# RLC.net
KiCad netlist of a schematic drawn in Altium Designer
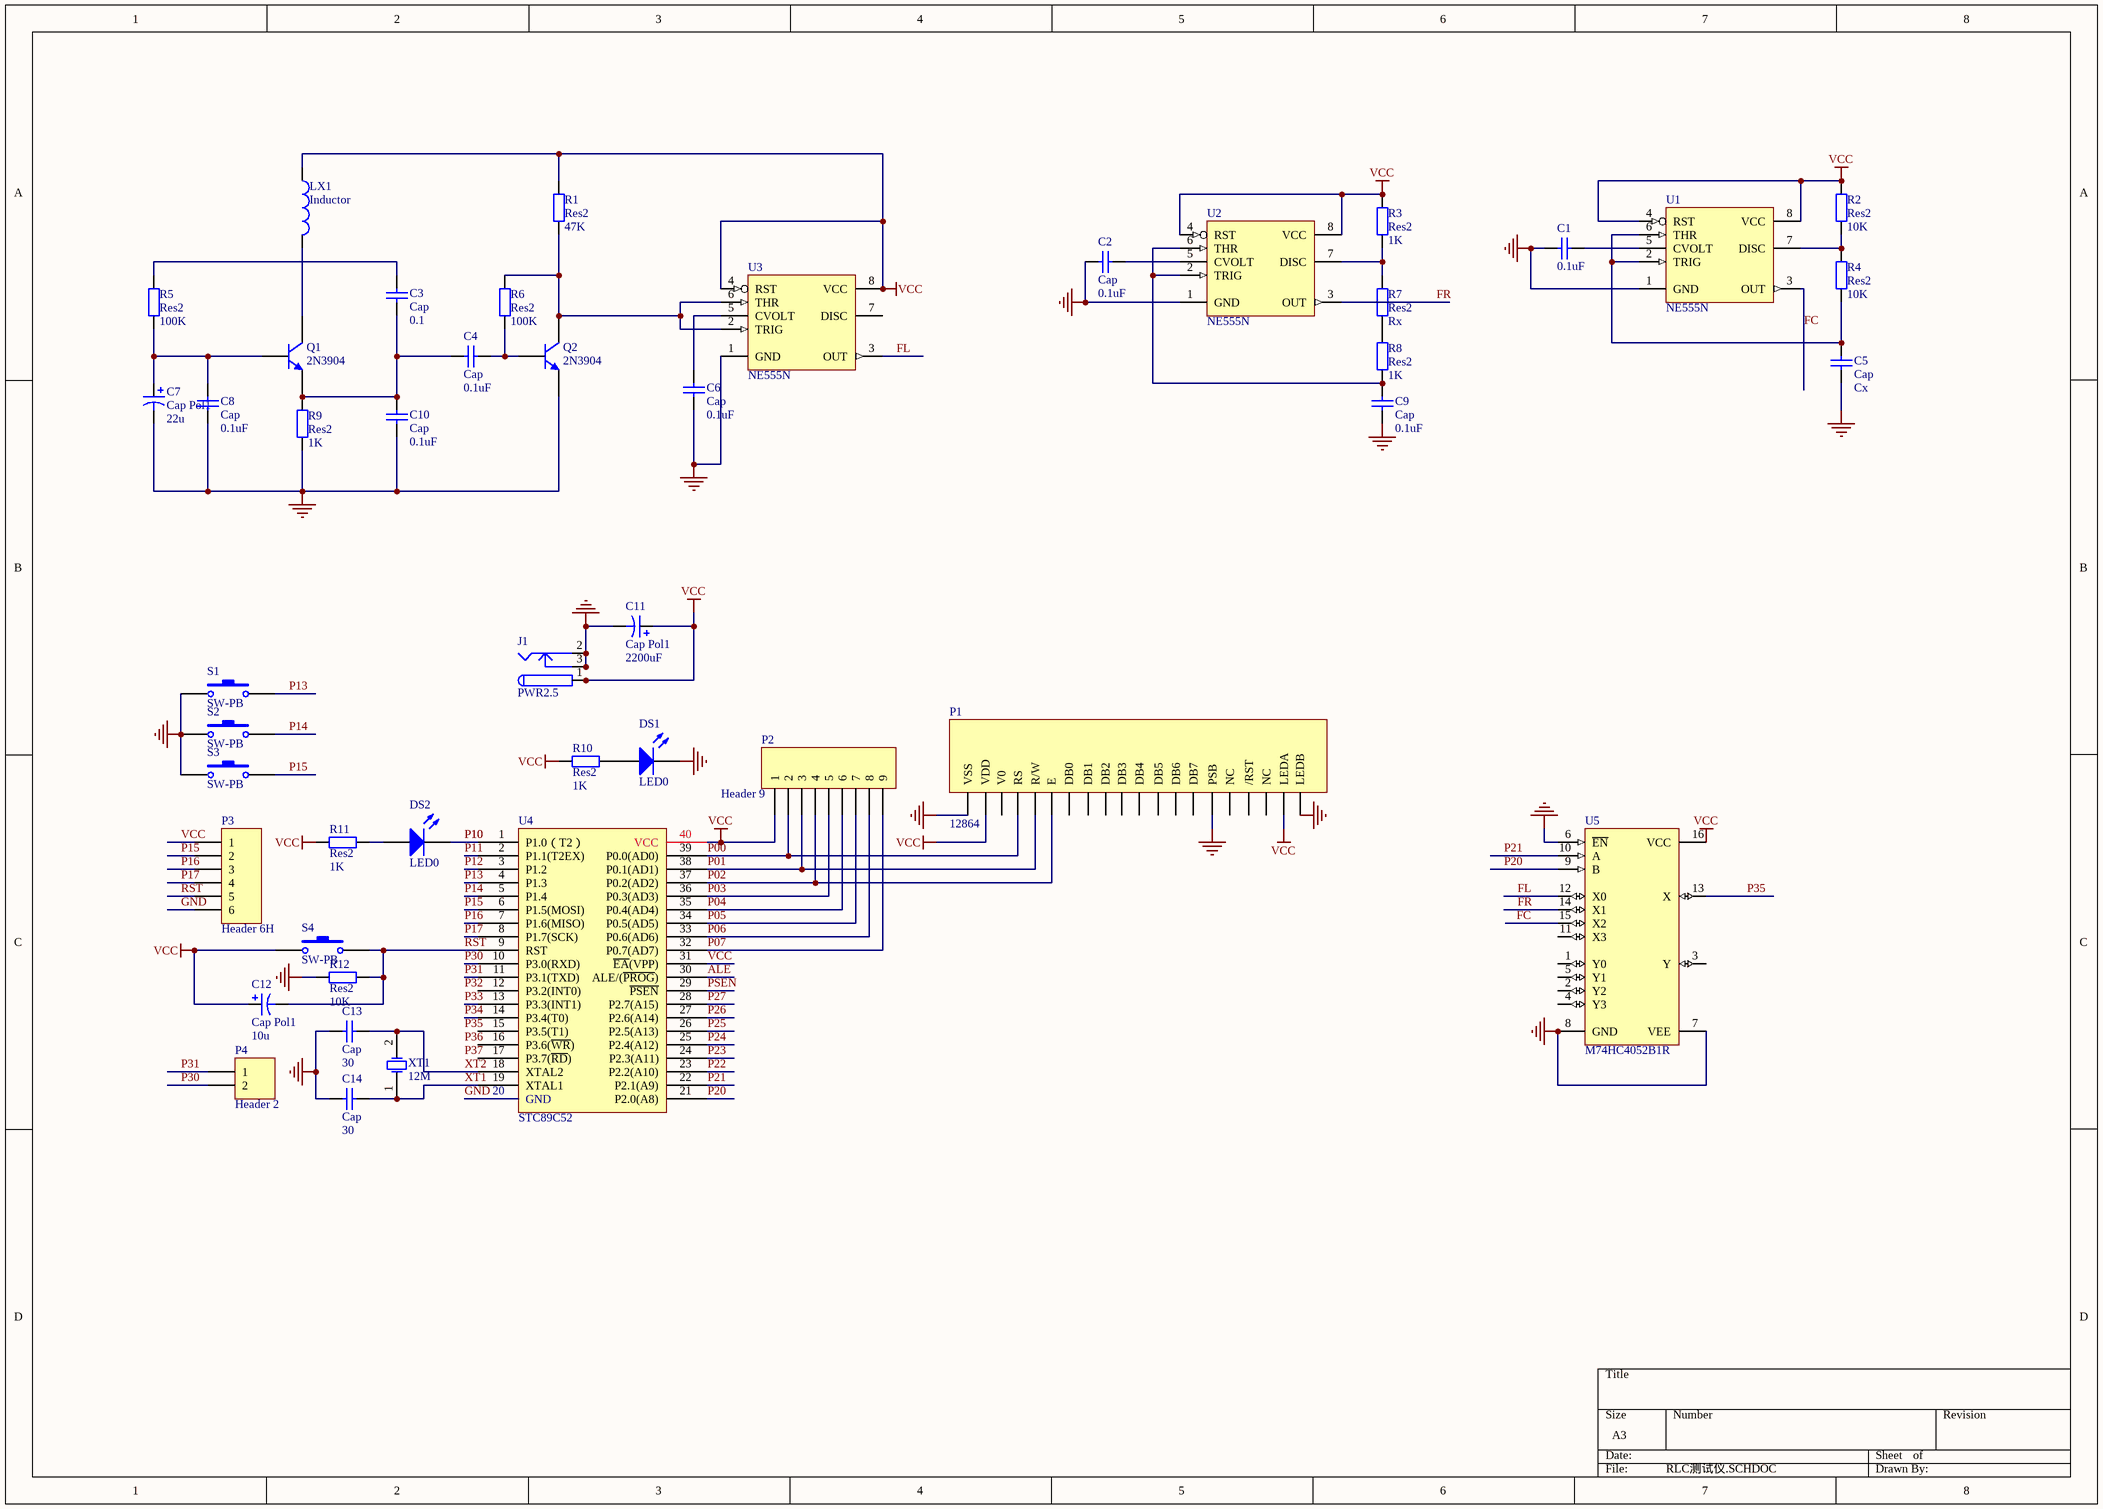
[diagram p0: RLC测试仪.SCHDOC]

(export (version "E")
  (design (tool "Eeschema 10.0.6"))
  (components
    (comp (ref "C1")
      (value "0.1uF")
      (footprint "RAD-0.2")
      (description "Capacitor")
      (fields (field (name "PUBLISHER") "Altium Limited"))
      (libsource (lib "Miscellaneous Devices") (part "Cap"))
    )
    (comp (ref "C2")
      (value "Cap")
      (footprint "RAD-0.2")
      (description "Capacitor")
      (fields (field (name "ALTIUM_VALUE") "0.1uF") (field (name "PUBLISHER") "Altium Limited"))
      (libsource (lib "Miscellaneous Devices") (part "Cap"))
    )
    (comp (ref "C3")
      (value "Cap")
      (footprint "RAD-0.2")
      (description "Capacitor")
      (fields (field (name "ALTIUM_VALUE") "0.1") (field (name "PUBLISHER") "Altium Limited"))
      (libsource (lib "Miscellaneous Devices") (part "Cap"))
    )
    (comp (ref "C4")
      (value "Cap")
      (footprint "RAD-0.2")
      (description "Capacitor")
      (fields (field (name "ALTIUM_VALUE") "0.1uF") (field (name "PUBLISHER") "Altium Limited"))
      (libsource (lib "Miscellaneous Devices") (part "Cap"))
    )
    (comp (ref "C5")
      (value "Cap")
      (footprint "RAD-0.2")
      (description "Capacitor")
      (fields (field (name "ALTIUM_VALUE") "Cx") (field (name "PUBLISHER") "Altium Limited"))
      (libsource (lib "Miscellaneous Devices") (part "Cap"))
    )
    (comp (ref "C6")
      (value "Cap")
      (footprint "RAD-0.2")
      (description "Capacitor")
      (fields (field (name "ALTIUM_VALUE") "0.1uF") (field (name "PUBLISHER") "Altium Limited"))
      (libsource (lib "Miscellaneous Devices") (part "Cap"))
    )
    (comp (ref "C7")
      (value "Cap Pol1")
      (footprint "电容")
      (description "Polarized Capacitor (Radial)")
      (fields (field (name "ALTIUM_VALUE") "22u") (field (name "PUBLISHER") "Altium Limited"))
      (libsource (lib "Miscellaneous Devices") (part "Cap Pol1"))
    )
    (comp (ref "C8")
      (value "Cap")
      (footprint "RAD-0.2")
      (description "Capacitor")
      (fields (field (name "ALTIUM_VALUE") "0.1uF") (field (name "PUBLISHER") "Altium Limited"))
      (libsource (lib "Miscellaneous Devices") (part "Cap"))
    )
    (comp (ref "C9")
      (value "Cap")
      (footprint "RAD-0.2")
      (description "Capacitor")
      (fields (field (name "ALTIUM_VALUE") "0.1uF") (field (name "PUBLISHER") "Altium Limited"))
      (libsource (lib "Miscellaneous Devices") (part "Cap"))
    )
    (comp (ref "C10")
      (value "Cap")
      (footprint "RAD-0.2")
      (description "Capacitor")
      (fields (field (name "ALTIUM_VALUE") "0.1uF") (field (name "PUBLISHER") "Altium Limited"))
      (libsource (lib "Miscellaneous Devices") (part "Cap"))
    )
    (comp (ref "C11")
      (value "Cap Pol1")
      (footprint "电容")
      (description "Polarized Capacitor (Radial)")
      (fields (field (name "ALTIUM_VALUE") "2200uF") (field (name "PUBLISHER") "Altium Limited"))
      (libsource (lib "Miscellaneous Devices") (part "Cap Pol1"))
    )
    (comp (ref "C12")
      (value "Cap Pol1")
      (footprint "电容")
      (description "Polarized Capacitor (Radial)")
      (fields (field (name "ALTIUM_VALUE") "10u") (field (name "PUBLISHER") "Altium Limited"))
      (libsource (lib "Miscellaneous Devices") (part "Cap Pol1"))
    )
    (comp (ref "C13")
      (value "Cap")
      (footprint "RAD-0.1")
      (description "Capacitor")
      (fields (field (name "ALTIUM_VALUE") "30") (field (name "PUBLISHER") "Altium Limited"))
      (libsource (lib "Miscellaneous Devices") (part "Cap"))
    )
    (comp (ref "C14")
      (value "Cap")
      (footprint "RAD-0.1")
      (description "Capacitor")
      (fields (field (name "ALTIUM_VALUE") "30") (field (name "PUBLISHER") "Altium Limited"))
      (libsource (lib "Miscellaneous Devices") (part "Cap"))
    )
    (comp (ref "DS1")
      (value "LED0")
      (footprint "RAD-0.1")
      (description "Typical INFRARED GaAs LED")
      (fields (field (name "PUBLISHER") "Altium Limited"))
      (libsource (lib "Miscellaneous Devices") (part "LED0"))
    )
    (comp (ref "DS2")
      (value "LED0")
      (footprint "RAD-0.1")
      (description "Typical INFRARED GaAs LED")
      (fields (field (name "PUBLISHER") "Altium Limited"))
      (libsource (lib "Miscellaneous Devices") (part "LED0"))
    )
    (comp (ref "J1")
      (value "PWR2.5")
      (footprint "KLD-0202")
      (description "Low Voltage Power Supply Connector")
      (fields (field (name "PUBLISHER") "Altium Limited"))
      (libsource (lib "Miscellaneous Connectors") (part "PWR2.5"))
    )
    (comp (ref "LX1")
      (value "Inductor")
      (footprint "RAD-0.3")
      (fields (field (name "PUBLISHER") "Altium Limited"))
      (libsource (lib "Miscellaneous Devices") (part "Inductor"))
    )
    (comp (ref "P1") (value "12864") (footprint "HDR1X20") (libsource (lib "我的原理图库.") (part "12864")))
    (comp (ref "P2")
      (value "Header 9")
      (footprint "HDR1X9")
      (description "Header, 9-Pin")
      (fields (field (name "PUBLISHER") "Altium Limited"))
      (libsource (lib "Miscellaneous Connectors") (part "Header 9"))
    )
    (comp (ref "P3")
      (value "Header 6H")
      (footprint "HDR1X6")
      (description "Header, 6-Pin, Right Angle")
      (fields (field (name "PUBLISHER") "Altium Limited"))
      (libsource (lib "Miscellaneous Connectors") (part "Header 6H"))
    )
    (comp (ref "P4")
      (value "Header 2")
      (footprint "HDR1X2")
      (description "Header, 2-Pin")
      (fields (field (name "PUBLISHER") "Altium Limited"))
      (libsource (lib "Miscellaneous Connectors") (part "Header 2"))
    )
    (comp (ref "Q1")
      (value "2N3904")
      (footprint "BCY-W3/E4")
      (description "NPN General Purpose Amplifier")
      (fields (field (name "PUBLISHER") "Altium Limited"))
      (libsource (lib "Miscellaneous Devices") (part "2N3904"))
    )
    (comp (ref "Q2")
      (value "2N3904")
      (footprint "BCY-W3/E4")
      (description "NPN General Purpose Amplifier")
      (fields (field (name "PUBLISHER") "Altium Limited"))
      (libsource (lib "Miscellaneous Devices") (part "2N3904"))
    )
    (comp (ref "R1")
      (value "Res2")
      (footprint "AXIAL-0.4")
      (description "Resistor")
      (fields (field (name "ALTIUM_VALUE") "47K") (field (name "PUBLISHER") "Altium Limited"))
      (libsource (lib "") (part "Res2_1"))
    )
    (comp (ref "R2")
      (value "Res2")
      (footprint "AXIAL-0.4")
      (description "Resistor")
      (fields (field (name "ALTIUM_VALUE") "10K") (field (name "PUBLISHER") "Altium Limited"))
      (libsource (lib "") (part "Res2_1"))
    )
    (comp (ref "R3")
      (value "Res2")
      (footprint "AXIAL-0.4")
      (description "Resistor")
      (fields (field (name "ALTIUM_VALUE") "1K") (field (name "PUBLISHER") "Altium Limited"))
      (libsource (lib "") (part "Res2_1"))
    )
    (comp (ref "R4")
      (value "Res2")
      (footprint "AXIAL-0.4")
      (description "Resistor")
      (fields (field (name "ALTIUM_VALUE") "10K") (field (name "PUBLISHER") "Altium Limited"))
      (libsource (lib "") (part "Res2_1"))
    )
    (comp (ref "R5")
      (value "Res2")
      (footprint "AXIAL-0.4")
      (description "Resistor")
      (fields (field (name "ALTIUM_VALUE") "100K") (field (name "PUBLISHER") "Altium Limited"))
      (libsource (lib "") (part "Res2_1"))
    )
    (comp (ref "R6")
      (value "Res2")
      (footprint "AXIAL-0.4")
      (description "Resistor")
      (fields (field (name "ALTIUM_VALUE") "100K") (field (name "PUBLISHER") "Altium Limited"))
      (libsource (lib "") (part "Res2_2"))
    )
    (comp (ref "R7")
      (value "Res2")
      (footprint "AXIAL-0.4")
      (description "Resistor")
      (fields (field (name "ALTIUM_VALUE") "Rx") (field (name "PUBLISHER") "Altium Limited"))
      (libsource (lib "") (part "Res2_1"))
    )
    (comp (ref "R8")
      (value "Res2")
      (footprint "AXIAL-0.4")
      (description "Resistor")
      (fields (field (name "ALTIUM_VALUE") "1K") (field (name "PUBLISHER") "Altium Limited"))
      (libsource (lib "") (part "Res2_2"))
    )
    (comp (ref "R9")
      (value "Res2")
      (footprint "AXIAL-0.4")
      (description "Resistor")
      (fields (field (name "ALTIUM_VALUE") "1K") (field (name "PUBLISHER") "Altium Limited"))
      (libsource (lib "") (part "Res2_1"))
    )
    (comp (ref "R10")
      (value "Res2")
      (footprint "AXIAL-0.4")
      (description "Resistor")
      (fields (field (name "ALTIUM_VALUE") "1K") (field (name "PUBLISHER") "Altium Limited"))
      (libsource (lib "") (part "Res2_3"))
    )
    (comp (ref "R11")
      (value "Res2")
      (footprint "AXIAL-0.4")
      (description "Resistor")
      (fields (field (name "ALTIUM_VALUE") "1K") (field (name "PUBLISHER") "Altium Limited"))
      (libsource (lib "Miscellaneous Devices") (part "Res2"))
    )
    (comp (ref "R12")
      (value "Res2")
      (footprint "AXIAL-0.4")
      (description "Resistor")
      (fields (field (name "ALTIUM_VALUE") "10K") (field (name "PUBLISHER") "Altium Limited"))
      (libsource (lib "") (part "Res2_3"))
    )
    (comp (ref "S1")
      (value "SW-PB")
      (footprint "点动按键")
      (description "Switch")
      (fields (field (name "PUBLISHER") "Altium Limited"))
      (libsource (lib "Miscellaneous Devices") (part "SW-PB"))
    )
    (comp (ref "S2")
      (value "SW-PB")
      (footprint "点动按键")
      (description "Switch")
      (fields (field (name "PUBLISHER") "Altium Limited"))
      (libsource (lib "Miscellaneous Devices") (part "SW-PB"))
    )
    (comp (ref "S3")
      (value "SW-PB")
      (footprint "点动按键")
      (description "Switch")
      (fields (field (name "PUBLISHER") "Altium Limited"))
      (libsource (lib "Miscellaneous Devices") (part "SW-PB"))
    )
    (comp (ref "S4")
      (value "SW-PB")
      (footprint "点动按键")
      (description "Switch")
      (fields (field (name "PUBLISHER") "Altium Limited"))
      (libsource (lib "Miscellaneous Devices") (part "SW-PB"))
    )
    (comp (ref "U1")
      (value "NE555N")
      (footprint "DIP8")
      (description "General-Purpose Single Bipolar Timer")
      (fields (field (name "PUBLISHER") "Altium Limited"))
      (libsource (lib "ST Analog Timer Circuit") (part "NE555N"))
    )
    (comp (ref "U2")
      (value "NE555N")
      (footprint "DIP8")
      (description "General-Purpose Single Bipolar Timer")
      (fields (field (name "PUBLISHER") "Altium Limited"))
      (libsource (lib "ST Analog Timer Circuit") (part "NE555N"))
    )
    (comp (ref "U3")
      (value "NE555N")
      (footprint "DIP8")
      (description "General-Purpose Single Bipolar Timer")
      (fields (field (name "PUBLISHER") "Altium Limited"))
      (libsource (lib "ST Analog Timer Circuit") (part "NE555N"))
    )
    (comp (ref "U4")
      (value "STC89C52")
      (footprint "AT89S52")
      (libsource (lib "原理图lanzhengfaSchlib1") (part "AT89S52"))
    )
    (comp (ref "U5")
      (value "M74HC4052B1R")
      (footprint "DIP16")
      (description "Analog Multiplexer/Demultiplexer Dual 4-Channel")
      (fields (field (name "PUBLISHER") "Altium Limited"))
      (libsource (lib "altium-import") (part "root_0_M74HC4052B1R_"))
    )
    (comp (ref "XT1") (value "12M") (footprint "圆晶振") (libsource (lib "原理图lanzhengfaSchlib1") (part "XTAL2")))
  )
  (nets
    (net (code "1") (name "/ALE") (class "Default")
      (node (ref "U4") (pin "30") (pinfunction "ALE/(~{PROG})_30") (pintype "passive"))
    )
    (net (code "2") (name "/FC") (class "Default")
      (node (ref "U1") (pin "3") (pinfunction "OUT_3") (pintype "output"))
      (node (ref "U5") (pin "15") (pinfunction "X2_15") (pintype "bidirectional"))
    )
    (net (code "3") (name "/FL") (class "Default")
      (node (ref "U3") (pin "3") (pinfunction "OUT_3") (pintype "output"))
      (node (ref "U5") (pin "12") (pinfunction "X0_12") (pintype "bidirectional"))
    )
    (net (code "4") (name "/FR") (class "Default")
      (node (ref "U2") (pin "3") (pinfunction "OUT_3") (pintype "output"))
      (node (ref "U5") (pin "14") (pinfunction "X1_14") (pintype "bidirectional"))
    )
    (net (code "5") (name "/P00") (class "Default")
      (node (ref "P1") (pin "4") (pinfunction "RS_4") (pintype "passive"))
      (node (ref "P2") (pin "2") (pinfunction "2_2") (pintype "passive"))
      (node (ref "U4") (pin "39") (pinfunction "P0.0(AD0)_39") (pintype "passive"))
    )
    (net (code "6") (name "/P01") (class "Default")
      (node (ref "P1") (pin "5") (pinfunction "R/W_5") (pintype "passive"))
      (node (ref "P2") (pin "3") (pinfunction "3_3") (pintype "passive"))
      (node (ref "U4") (pin "38") (pinfunction "P0.1(AD1)_38") (pintype "passive"))
    )
    (net (code "7") (name "/P02") (class "Default")
      (node (ref "P1") (pin "6") (pinfunction "E_6") (pintype "passive"))
      (node (ref "P2") (pin "4") (pinfunction "4_4") (pintype "passive"))
      (node (ref "U4") (pin "37") (pinfunction "P0.2(AD2)_37") (pintype "passive"))
    )
    (net (code "8") (name "/P03") (class "Default")
      (node (ref "P2") (pin "5") (pinfunction "5_5") (pintype "passive"))
      (node (ref "U4") (pin "36") (pinfunction "P0.3(AD3)_36") (pintype "passive"))
    )
    (net (code "9") (name "/P04") (class "Default")
      (node (ref "P2") (pin "6") (pinfunction "6_6") (pintype "passive"))
      (node (ref "U4") (pin "35") (pinfunction "P0.4(AD4)_35") (pintype "passive"))
    )
    (net (code "10") (name "/P05") (class "Default")
      (node (ref "P2") (pin "7") (pinfunction "7_7") (pintype "passive"))
      (node (ref "U4") (pin "34") (pinfunction "P0.5(AD5)_34") (pintype "passive"))
    )
    (net (code "11") (name "/P06") (class "Default")
      (node (ref "P2") (pin "8") (pinfunction "8_8") (pintype "passive"))
      (node (ref "U4") (pin "33") (pinfunction "P0.6(AD6)_33") (pintype "passive"))
    )
    (net (code "12") (name "/P07") (class "Default")
      (node (ref "P2") (pin "9") (pinfunction "9_9") (pintype "passive"))
      (node (ref "U4") (pin "32") (pinfunction "P0.7(AD7)_32") (pintype "passive"))
    )
    (net (code "13") (name "/P10") (class "Default")
      (node (ref "DS2") (pin "2") (pinfunction "K_2") (pintype "passive"))
      (node (ref "U4") (pin "1") (pinfunction "P1.0（T2）_1") (pintype "passive"))
    )
    (net (code "14") (name "/P11") (class "Default")
      (node (ref "U4") (pin "2") (pinfunction "P1.1(T2EX)_2") (pintype "passive"))
    )
    (net (code "15") (name "/P12") (class "Default")
      (node (ref "U4") (pin "3") (pinfunction "P1.2_3") (pintype "passive"))
    )
    (net (code "16") (name "/P13") (class "Default")
      (node (ref "S1") (pin "2") (pinfunction "2_2") (pintype "passive"))
      (node (ref "U4") (pin "4") (pinfunction "P1.3_4") (pintype "passive"))
    )
    (net (code "17") (name "/P14") (class "Default")
      (node (ref "S2") (pin "2") (pinfunction "2_2") (pintype "passive"))
      (node (ref "U4") (pin "5") (pinfunction "P1.4_5") (pintype "passive"))
    )
    (net (code "18") (name "/P15") (class "Default")
      (node (ref "P3") (pin "2") (pinfunction "2_2") (pintype "passive"))
      (node (ref "S3") (pin "2") (pinfunction "2_2") (pintype "passive"))
      (node (ref "U4") (pin "6") (pinfunction "P1.5(MOSI)_6") (pintype "passive"))
    )
    (net (code "19") (name "/P16") (class "Default")
      (node (ref "P3") (pin "3") (pinfunction "3_3") (pintype "passive"))
      (node (ref "U4") (pin "7") (pinfunction "P1.6(MISO)_7") (pintype "passive"))
    )
    (net (code "20") (name "/P17") (class "Default")
      (node (ref "P3") (pin "4") (pinfunction "4_4") (pintype "passive"))
      (node (ref "U4") (pin "8") (pinfunction "P1.7(SCK)_8") (pintype "passive"))
    )
    (net (code "21") (name "/P20") (class "Default")
      (node (ref "U4") (pin "21") (pinfunction "P2.0(A8)_21") (pintype "passive"))
      (node (ref "U5") (pin "9") (pinfunction "B_9") (pintype "input"))
    )
    (net (code "22") (name "/P21") (class "Default")
      (node (ref "U4") (pin "22") (pinfunction "P2.1(A9)_22") (pintype "passive"))
      (node (ref "U5") (pin "10") (pinfunction "A_10") (pintype "input"))
    )
    (net (code "23") (name "/P22") (class "Default")
      (node (ref "U4") (pin "23") (pinfunction "P2.2(A10)_23") (pintype "passive"))
    )
    (net (code "24") (name "/P23") (class "Default")
      (node (ref "U4") (pin "24") (pinfunction "P2.3(A11)_24") (pintype "passive"))
    )
    (net (code "25") (name "/P24") (class "Default")
      (node (ref "U4") (pin "25") (pinfunction "P2.4(A12)_25") (pintype "passive"))
    )
    (net (code "26") (name "/P25") (class "Default")
      (node (ref "U4") (pin "26") (pinfunction "P2.5(A13)_26") (pintype "passive"))
    )
    (net (code "27") (name "/P26") (class "Default")
      (node (ref "U4") (pin "27") (pinfunction "P2.6(A14)_27") (pintype "passive"))
    )
    (net (code "28") (name "/P27") (class "Default")
      (node (ref "U4") (pin "28") (pinfunction "P2.7(A15)_28") (pintype "passive"))
    )
    (net (code "29") (name "/P30") (class "Default")
      (node (ref "P4") (pin "2") (pinfunction "2_2") (pintype "passive"))
      (node (ref "U4") (pin "10") (pinfunction "P3.0(RXD)_10") (pintype "passive"))
    )
    (net (code "30") (name "/P31") (class "Default")
      (node (ref "P4") (pin "1") (pinfunction "1_1") (pintype "passive"))
      (node (ref "U4") (pin "11") (pinfunction "P3.1(TXD)_11") (pintype "passive"))
    )
    (net (code "32") (name "/P33") (class "Default")
      (node (ref "U4") (pin "13") (pinfunction "P3.3(INT1)_13") (pintype "passive"))
    )
    (net (code "33") (name "/P34") (class "Default")
      (node (ref "U4") (pin "14") (pinfunction "P3.4(T0)_14") (pintype "passive"))
    )
    (net (code "34") (name "/P35") (class "Default")
      (node (ref "U5") (pin "13") (pinfunction "X_13") (pintype "bidirectional"))
    )
    (net (code "37") (name "/PSEN") (class "Default")
      (node (ref "U4") (pin "29") (pinfunction "~{PSEN}_29") (pintype "passive"))
    )
    (net (code "38") (name "/RST") (class "Default")
      (node (ref "C12") (pin "2") (pinfunction "2_2") (pintype "passive"))
      (node (ref "P3") (pin "5") (pinfunction "5_5") (pintype "passive"))
      (node (ref "R12") (pin "2") (pinfunction "2_2") (pintype "passive"))
      (node (ref "S4") (pin "2") (pinfunction "2_2") (pintype "passive"))
      (node (ref "U4") (pin "9") (pinfunction "RST_9") (pintype "passive"))
    )
    (net (code "39") (name "/XT1") (class "Default")
      (node (ref "C14") (pin "2") (pinfunction "2_2") (pintype "passive"))
      (node (ref "U4") (pin "19") (pinfunction "XTAL1_19") (pintype "passive"))
      (node (ref "XT1") (pin "1") (pinfunction "OSC1_1") (pintype "passive"))
    )
    (net (code "40") (name "/XT2") (class "Default")
      (node (ref "C13") (pin "2") (pinfunction "2_2") (pintype "passive"))
      (node (ref "U4") (pin "18") (pinfunction "XTAL2_18") (pintype "passive"))
      (node (ref "XT1") (pin "2") (pinfunction "OSC2_2") (pintype "passive"))
    )
    (net (code "41") (name "GND") (class "Default")
      (node (ref "C1") (pin "2") (pinfunction "2_2") (pintype "passive"))
      (node (ref "C10") (pin "1") (pinfunction "1_1") (pintype "passive"))
      (node (ref "C11") (pin "2") (pinfunction "2_2") (pintype "passive"))
      (node (ref "C13") (pin "1") (pinfunction "1_1") (pintype "passive"))
      (node (ref "C14") (pin "1") (pinfunction "1_1") (pintype "passive"))
      (node (ref "C2") (pin "2") (pinfunction "2_2") (pintype "passive"))
      (node (ref "C5") (pin "1") (pinfunction "1_1") (pintype "passive"))
      (node (ref "C6") (pin "2") (pinfunction "2_2") (pintype "passive"))
      (node (ref "C7") (pin "2") (pinfunction "2_2") (pintype "passive"))
      (node (ref "C8") (pin "1") (pinfunction "1_1") (pintype "passive"))
      (node (ref "C9") (pin "1") (pinfunction "1_1") (pintype "passive"))
      (node (ref "DS1") (pin "2") (pinfunction "K_2") (pintype "passive"))
      (node (ref "J1") (pin "2") (pinfunction "2_2") (pintype "power_in"))
      (node (ref "J1") (pin "2A") (pinfunction "2A_2A") (pintype "power_in"))
      (node (ref "J1") (pin "2B") (pinfunction "2B_2B") (pintype "power_in"))
      (node (ref "J1") (pin "3") (pinfunction "3_3") (pintype "power_in"))
      (node (ref "J1") (pin "3A") (pinfunction "3A_3A") (pintype "power_in"))
      (node (ref "J1") (pin "3B") (pinfunction "3B_3B") (pintype "power_in"))
      (node (ref "P1") (pin "1") (pinfunction "VSS_1") (pintype "passive"))
      (node (ref "P1") (pin "15") (pinfunction "PSB_15") (pintype "passive"))
      (node (ref "P1") (pin "20") (pinfunction "LEDB_20") (pintype "passive"))
      (node (ref "P3") (pin "6") (pinfunction "6_6") (pintype "passive"))
      (node (ref "Q2") (pin "1") (pinfunction "E_1") (pintype "passive"))
      (node (ref "R12") (pin "1") (pinfunction "1_1") (pintype "passive"))
      (node (ref "R9") (pin "1") (pinfunction "1_1") (pintype "passive"))
      (node (ref "S1") (pin "1") (pinfunction "1_1") (pintype "passive"))
      (node (ref "S2") (pin "1") (pinfunction "1_1") (pintype "passive"))
      (node (ref "S3") (pin "1") (pinfunction "1_1") (pintype "passive"))
      (node (ref "U1") (pin "1") (pinfunction "GND_1") (pintype "power_in"))
      (node (ref "U2") (pin "1") (pinfunction "GND_1") (pintype "power_in"))
      (node (ref "U3") (pin "1") (pinfunction "GND_1") (pintype "power_in"))
      (node (ref "U4") (pin "20") (pinfunction "GND_20") (pintype "passive"))
      (node (ref "U5") (pin "6") (pinfunction "~{EN}_6") (pintype "input"))
      (node (ref "U5") (pin "7") (pinfunction "VEE_7") (pintype "power_in"))
      (node (ref "U5") (pin "8") (pinfunction "GND_8") (pintype "power_in"))
    )
    (net (code "42") (name "Net-(C3-Pad2)") (class "Default")
      (node (ref "C3") (pin "2") (pinfunction "2_2") (pintype "passive"))
      (node (ref "R5") (pin "2") (pinfunction "2_2") (pintype "passive"))
    )
    (net (code "43") (name "Net-(DS1-A)") (class "Default")
      (node (ref "DS1") (pin "1") (pinfunction "A_1") (pintype "passive"))
      (node (ref "R10") (pin "2") (pinfunction "2_2") (pintype "passive"))
    )
    (net (code "44") (name "Net-(DS2-A)") (class "Default")
      (node (ref "DS2") (pin "1") (pinfunction "A_1") (pintype "passive"))
      (node (ref "R11") (pin "1") (pinfunction "1_1") (pintype "passive"))
    )
    (net (code "45") (name "Net-(Q1-B)") (class "Default")
      (node (ref "C7") (pin "1") (pinfunction "1_1") (pintype "passive"))
      (node (ref "C8") (pin "2") (pinfunction "2_2") (pintype "passive"))
      (node (ref "Q1") (pin "2") (pinfunction "B_2") (pintype "passive"))
      (node (ref "R5") (pin "1") (pinfunction "1_1") (pintype "passive"))
    )
    (net (code "46") (name "Net-(Q1-C)") (class "Default")
      (node (ref "LX1") (pin "2") (pinfunction "2_2") (pintype "passive"))
      (node (ref "Q1") (pin "3") (pinfunction "C_3") (pintype "passive"))
    )
    (net (code "47") (name "Net-(Q1-E)") (class "Default")
      (node (ref "C10") (pin "2") (pinfunction "2_2") (pintype "passive"))
      (node (ref "C3") (pin "1") (pinfunction "1_1") (pintype "passive"))
      (node (ref "C4") (pin "2") (pinfunction "2_2") (pintype "passive"))
      (node (ref "Q1") (pin "1") (pinfunction "E_1") (pintype "passive"))
      (node (ref "R9") (pin "2") (pinfunction "2_2") (pintype "passive"))
    )
    (net (code "48") (name "Net-(Q2-B)") (class "Default")
      (node (ref "C4") (pin "1") (pinfunction "1_1") (pintype "passive"))
      (node (ref "Q2") (pin "2") (pinfunction "B_2") (pintype "passive"))
      (node (ref "R6") (pin "2") (pinfunction "2_2") (pintype "passive"))
    )
    (net (code "49") (name "Net-(Q2-C)") (class "Default")
      (node (ref "Q2") (pin "3") (pinfunction "C_3") (pintype "passive"))
      (node (ref "R1") (pin "1") (pinfunction "1_1") (pintype "passive"))
      (node (ref "R6") (pin "1") (pinfunction "1_1") (pintype "passive"))
      (node (ref "U3") (pin "2") (pinfunction "TRIG_2") (pintype "input"))
      (node (ref "U3") (pin "6") (pinfunction "THR_6") (pintype "input"))
    )
    (net (code "50") (name "Net-(R7-Pad1)") (class "Default")
      (node (ref "R7") (pin "1") (pinfunction "1_1") (pintype "passive"))
      (node (ref "R8") (pin "1") (pinfunction "1_1") (pintype "passive"))
    )
    (net (code "51") (name "Net-(U1-CVOLT)") (class "Default")
      (node (ref "C1") (pin "1") (pinfunction "1_1") (pintype "passive"))
      (node (ref "U1") (pin "5") (pinfunction "CVOLT_5") (pintype "passive"))
    )
    (net (code "52") (name "Net-(U1-DISC)") (class "Default")
      (node (ref "R2") (pin "1") (pinfunction "1_1") (pintype "passive"))
      (node (ref "R4") (pin "2") (pinfunction "2_2") (pintype "passive"))
      (node (ref "U1") (pin "7") (pinfunction "DISC_7") (pintype "open_collector"))
    )
    (net (code "53") (name "Net-(U1-THR)") (class "Default")
      (node (ref "C5") (pin "2") (pinfunction "2_2") (pintype "passive"))
      (node (ref "R4") (pin "1") (pinfunction "1_1") (pintype "passive"))
      (node (ref "U1") (pin "2") (pinfunction "TRIG_2") (pintype "input"))
      (node (ref "U1") (pin "6") (pinfunction "THR_6") (pintype "input"))
    )
    (net (code "54") (name "Net-(U2-CVOLT)") (class "Default")
      (node (ref "C2") (pin "1") (pinfunction "1_1") (pintype "passive"))
      (node (ref "U2") (pin "5") (pinfunction "CVOLT_5") (pintype "passive"))
    )
    (net (code "55") (name "Net-(U2-DISC)") (class "Default")
      (node (ref "R3") (pin "1") (pinfunction "1_1") (pintype "passive"))
      (node (ref "R7") (pin "2") (pinfunction "2_2") (pintype "passive"))
      (node (ref "U2") (pin "7") (pinfunction "DISC_7") (pintype "open_collector"))
    )
    (net (code "56") (name "Net-(U2-THR)") (class "Default")
      (node (ref "C9") (pin "2") (pinfunction "2_2") (pintype "passive"))
      (node (ref "R8") (pin "2") (pinfunction "2_2") (pintype "passive"))
      (node (ref "U2") (pin "2") (pinfunction "TRIG_2") (pintype "input"))
      (node (ref "U2") (pin "6") (pinfunction "THR_6") (pintype "input"))
    )
    (net (code "57") (name "Net-(U3-CVOLT)") (class "Default")
      (node (ref "C6") (pin "1") (pinfunction "1_1") (pintype "passive"))
      (node (ref "U3") (pin "5") (pinfunction "CVOLT_5") (pintype "passive"))
    )
    (net (code "58") (name "VCC") (class "Default")
      (node (ref "C11") (pin "1") (pinfunction "1_1") (pintype "passive"))
      (node (ref "C12") (pin "1") (pinfunction "1_1") (pintype "passive"))
      (node (ref "J1") (pin "1") (pinfunction "1_1") (pintype "power_in"))
      (node (ref "J1") (pin "1A") (pinfunction "1A_1A") (pintype "power_in"))
      (node (ref "J1") (pin "1B") (pinfunction "1B_1B") (pintype "power_in"))
      (node (ref "LX1") (pin "1") (pinfunction "1_1") (pintype "passive"))
      (node (ref "P1") (pin "19") (pinfunction "LEDA_19") (pintype "passive"))
      (node (ref "P1") (pin "2") (pinfunction "VDD_2") (pintype "passive"))
      (node (ref "P2") (pin "1") (pinfunction "1_1") (pintype "passive"))
      (node (ref "P3") (pin "1") (pinfunction "1_1") (pintype "passive"))
      (node (ref "R1") (pin "2") (pinfunction "2_2") (pintype "passive"))
      (node (ref "R10") (pin "1") (pinfunction "1_1") (pintype "passive"))
      (node (ref "R11") (pin "2") (pinfunction "2_2") (pintype "passive"))
      (node (ref "R2") (pin "2") (pinfunction "2_2") (pintype "passive"))
      (node (ref "R3") (pin "2") (pinfunction "2_2") (pintype "passive"))
      (node (ref "S4") (pin "1") (pinfunction "1_1") (pintype "passive"))
      (node (ref "U1") (pin "4") (pinfunction "RST_4") (pintype "input"))
      (node (ref "U1") (pin "8") (pinfunction "VCC_8") (pintype "power_in"))
      (node (ref "U2") (pin "4") (pinfunction "RST_4") (pintype "input"))
      (node (ref "U2") (pin "8") (pinfunction "VCC_8") (pintype "power_in"))
      (node (ref "U3") (pin "4") (pinfunction "RST_4") (pintype "input"))
      (node (ref "U3") (pin "8") (pinfunction "VCC_8") (pintype "power_in"))
      (node (ref "U4") (pin "31") (pinfunction "~{EA}(VPP)_31") (pintype "passive"))
      (node (ref "U4") (pin "40") (pinfunction "VCC_40") (pintype "passive"))
      (node (ref "U5") (pin "16") (pinfunction "VCC_16") (pintype "power_in"))
    )
    (net (code "59") (name "unconnected-(P1-DB0-Pad7)") (class "Default")
      (node (ref "P1") (pin "7") (pinfunction "DB0_7") (pintype "passive"))
    )
    (net (code "60") (name "unconnected-(P1-DB1-Pad8)") (class "Default")
      (node (ref "P1") (pin "8") (pinfunction "DB1_8") (pintype "passive"))
    )
    (net (code "61") (name "unconnected-(P1-DB2-Pad9)") (class "Default")
      (node (ref "P1") (pin "9") (pinfunction "DB2_9") (pintype "passive"))
    )
    (net (code "62") (name "unconnected-(P1-DB3-Pad10)") (class "Default")
      (node (ref "P1") (pin "10") (pinfunction "DB3_10") (pintype "passive"))
    )
    (net (code "63") (name "unconnected-(P1-DB4-Pad11)") (class "Default")
      (node (ref "P1") (pin "11") (pinfunction "DB4_11") (pintype "passive"))
    )
    (net (code "64") (name "unconnected-(P1-DB5-Pad12)") (class "Default")
      (node (ref "P1") (pin "12") (pinfunction "DB5_12") (pintype "passive"))
    )
    (net (code "65") (name "unconnected-(P1-DB6-Pad13)") (class "Default")
      (node (ref "P1") (pin "13") (pinfunction "DB6_13") (pintype "passive"))
    )
    (net (code "66") (name "unconnected-(P1-DB7-Pad14)") (class "Default")
      (node (ref "P1") (pin "14") (pinfunction "DB7_14") (pintype "passive"))
    )
    (net (code "67") (name "unconnected-(P1-NC-Pad16)") (class "Default")
      (node (ref "P1") (pin "16") (pinfunction "NC_16") (pintype "passive"))
    )
    (net (code "68") (name "unconnected-(P1-NC-Pad18)") (class "Default")
      (node (ref "P1") (pin "18") (pinfunction "NC_18") (pintype "passive"))
    )
    (net (code "69") (name "unconnected-(P1-V0-Pad3)") (class "Default")
      (node (ref "P1") (pin "3") (pinfunction "V0_3") (pintype "passive"))
    )
    (net (code "70") (name "unconnected-(P1-{slash}RST-Pad17)") (class "Default")
      (node (ref "P1") (pin "17") (pinfunction "/RST_17") (pintype "passive"))
    )
    (net (code "71") (name "unconnected-(U3-DISC-Pad7)") (class "Default")
      (node (ref "U3") (pin "7") (pinfunction "DISC_7") (pintype "open_collector"))
    )
    (net (code "72") (name "unconnected-(U4-P3.2(INT0)-Pad12)") (class "Default")
      (node (ref "U4") (pin "12") (pinfunction "P3.2(INT0)_12") (pintype "passive"))
    )
    (net (code "73") (name "unconnected-(U4-P3.5(T1)-Pad15)") (class "Default")
      (node (ref "U4") (pin "15") (pinfunction "P3.5(T1)_15") (pintype "passive"))
    )
    (net (code "74") (name "unconnected-(U4-P3.6(~{WR})-Pad16)") (class "Default")
      (node (ref "U4") (pin "16") (pinfunction "P3.6(~{WR})_16") (pintype "passive"))
    )
    (net (code "75") (name "unconnected-(U4-P3.7(~{RD})-Pad17)") (class "Default")
      (node (ref "U4") (pin "17") (pinfunction "P3.7(~{RD})_17") (pintype "passive"))
    )
    (net (code "76") (name "unconnected-(U5-X3-Pad11)") (class "Default")
      (node (ref "U5") (pin "11") (pinfunction "X3_11") (pintype "bidirectional"))
    )
    (net (code "77") (name "unconnected-(U5-Y-Pad3)") (class "Default")
      (node (ref "U5") (pin "3") (pinfunction "Y_3") (pintype "bidirectional"))
    )
    (net (code "78") (name "unconnected-(U5-Y0-Pad1)") (class "Default")
      (node (ref "U5") (pin "1") (pinfunction "Y0_1") (pintype "bidirectional"))
    )
    (net (code "79") (name "unconnected-(U5-Y1-Pad5)") (class "Default")
      (node (ref "U5") (pin "5") (pinfunction "Y1_5") (pintype "bidirectional"))
    )
    (net (code "80") (name "unconnected-(U5-Y2-Pad2)") (class "Default")
      (node (ref "U5") (pin "2") (pinfunction "Y2_2") (pintype "bidirectional"))
    )
    (net (code "81") (name "unconnected-(U5-Y3-Pad4)") (class "Default")
      (node (ref "U5") (pin "4") (pinfunction "Y3_4") (pintype "bidirectional"))
    )
  )
)
